# LPC812_breakout_v0_8_no_lr.net
KiCad netlist of a schematic drawn in EAGLE
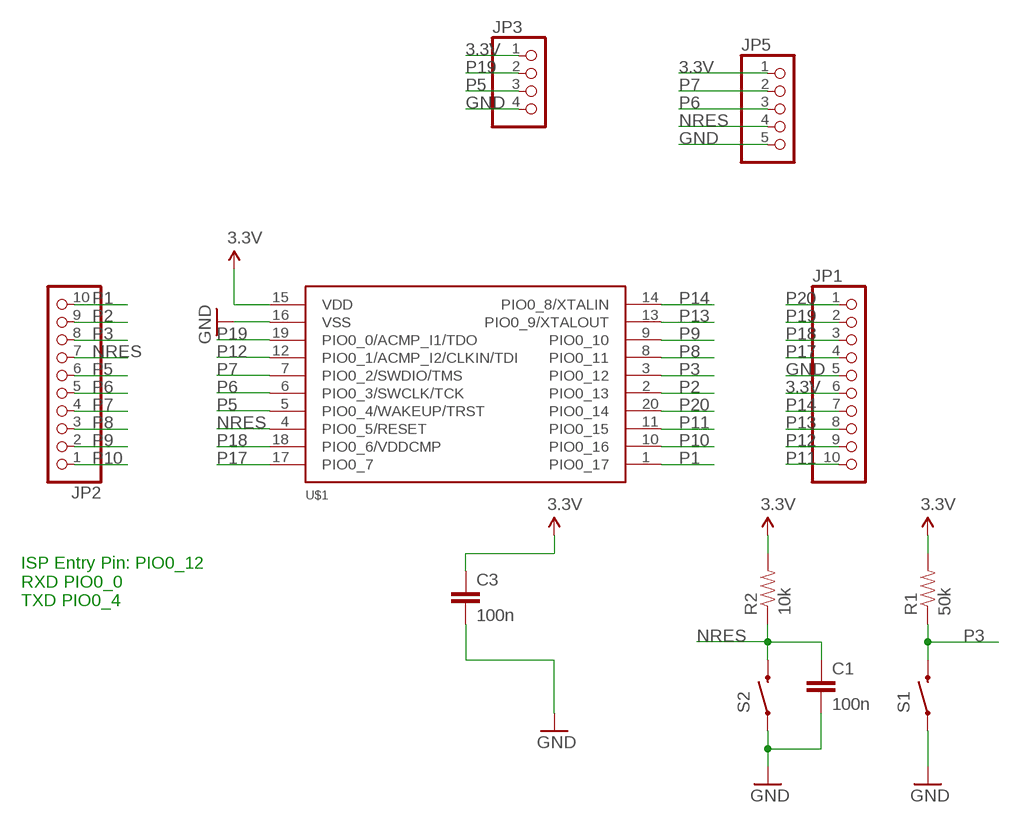
[diagram p0: schematic, sheet 1]

(export (version "E")
  (design (tool "Eeschema 10.0.6"))
  (components
    (comp (ref "C1")
      (value "100n")
      (footprint "eagle-import:0805")
      (libsource (lib "eagle-import") (part "CAP0805"))
    )
    (comp (ref "C3")
      (value "100n")
      (footprint "eagle-import:0805")
      (libsource (lib "eagle-import") (part "CAP0805"))
    )
    (comp (ref "JP1")
      (value "HEADER-1X10ROUND")
      (footprint "eagle-import:1X10_ROUND")
      (libsource (lib "eagle-import") (part "HEADER-1X10ROUND"))
    )
    (comp (ref "JP2")
      (value "HEADER-1X10ROUND")
      (footprint "eagle-import:1X10_ROUND")
      (libsource (lib "eagle-import") (part "HEADER-1X10ROUND"))
    )
    (comp (ref "JP3")
      (value "HEADER-1X4ROUND")
      (footprint "eagle-import:1X04_ROUND")
      (libsource (lib "eagle-import") (part "HEADER-1X4ROUND"))
    )
    (comp (ref "JP5")
      (value "HEADER-1X5ROUND")
      (footprint "eagle-import:1X05_ROUND")
      (libsource (lib "eagle-import") (part "HEADER-1X5ROUND"))
    )
    (comp (ref "R1")
      (value "50k")
      (footprint "eagle-import:0805")
      (libsource (lib "eagle-import") (part "RESISTOR0805-RES"))
    )
    (comp (ref "R2")
      (value "10k")
      (footprint "eagle-import:0805")
      (libsource (lib "eagle-import") (part "RESISTOR0805-RES"))
    )
    (comp (ref "S1")
      (value "SWITCH-MOMENTARY-2-SMD-1101NE")
      (footprint "eagle-import:TACTILE-SWITCH-1101NE")
      (libsource (lib "eagle-import") (part "SWITCH-MOMENTARY-2-SMD-1101NE"))
    )
    (comp (ref "S2")
      (value "SWITCH-MOMENTARY-2-SMD-1101NE")
      (footprint "eagle-import:TACTILE-SWITCH-1101NE")
      (libsource (lib "eagle-import") (part "SWITCH-MOMENTARY-2-SMD-1101NE"))
    )
    (comp (ref "U$1")
      (value "LPC812M101JDH20")
      (footprint "eagle-import:TSSOP20")
      (libsource (lib "eagle-import") (part "LPC812M101JDH20"))
    )
  )
  (nets
    (net (code "1") (name "/NRES") (class "Default")
      (node (ref "C1") (pin "1") (pinfunction "1_1") (pintype "passive"))
      (node (ref "JP2") (pin "7") (pinfunction "7_7") (pintype "passive"))
      (node (ref "JP5") (pin "4") (pinfunction "4_4") (pintype "passive"))
      (node (ref "R2") (pin "1") (pinfunction "1_1") (pintype "passive"))
      (node (ref "S2") (pin "P$2") (pinfunction "2_P$2") (pintype "passive"))
      (node (ref "U$1") (pin "4") (pinfunction "PIO0_5/RESET_4") (pintype "bidirectional"))
    )
    (net (code "2") (name "/P1") (class "Default")
      (node (ref "JP2") (pin "10") (pinfunction "10_10") (pintype "passive"))
      (node (ref "U$1") (pin "1") (pinfunction "PIO0_17_1") (pintype "bidirectional"))
    )
    (net (code "3") (name "/P2") (class "Default")
      (node (ref "JP2") (pin "9") (pinfunction "9_9") (pintype "passive"))
      (node (ref "U$1") (pin "2") (pinfunction "PIO0_13_2") (pintype "bidirectional"))
    )
    (net (code "4") (name "/P3") (class "Default")
      (node (ref "JP2") (pin "8") (pinfunction "8_8") (pintype "passive"))
      (node (ref "R1") (pin "1") (pinfunction "1_1") (pintype "passive"))
      (node (ref "S1") (pin "P$2") (pinfunction "2_P$2") (pintype "passive"))
      (node (ref "U$1") (pin "3") (pinfunction "PIO0_12_3") (pintype "bidirectional"))
    )
    (net (code "5") (name "/P5") (class "Default")
      (node (ref "JP2") (pin "6") (pinfunction "6_6") (pintype "passive"))
      (node (ref "JP3") (pin "3") (pinfunction "3_3") (pintype "passive"))
      (node (ref "U$1") (pin "5") (pinfunction "PIO0_4/WAKEUP/TRST_5") (pintype "bidirectional"))
    )
    (net (code "6") (name "/P6") (class "Default")
      (node (ref "JP2") (pin "5") (pinfunction "5_5") (pintype "passive"))
      (node (ref "JP5") (pin "3") (pinfunction "3_3") (pintype "passive"))
      (node (ref "U$1") (pin "6") (pinfunction "PIO0_3/SWCLK/TCK_6") (pintype "bidirectional"))
    )
    (net (code "7") (name "/P7") (class "Default")
      (node (ref "JP2") (pin "4") (pinfunction "4_4") (pintype "passive"))
      (node (ref "JP5") (pin "2") (pinfunction "2_2") (pintype "passive"))
      (node (ref "U$1") (pin "7") (pinfunction "PIO0_2/SWDIO/TMS_7") (pintype "bidirectional"))
    )
    (net (code "8") (name "/P8") (class "Default")
      (node (ref "JP2") (pin "3") (pinfunction "3_3") (pintype "passive"))
      (node (ref "U$1") (pin "8") (pinfunction "PIO0_11_8") (pintype "bidirectional"))
    )
    (net (code "9") (name "/P9") (class "Default")
      (node (ref "JP2") (pin "2") (pinfunction "2_2") (pintype "passive"))
      (node (ref "U$1") (pin "9") (pinfunction "PIO0_10_9") (pintype "bidirectional"))
    )
    (net (code "10") (name "/P10") (class "Default")
      (node (ref "JP2") (pin "1") (pinfunction "1_1") (pintype "passive"))
      (node (ref "U$1") (pin "10") (pinfunction "PIO0_16_10") (pintype "bidirectional"))
    )
    (net (code "11") (name "/P11") (class "Default")
      (node (ref "JP1") (pin "10") (pinfunction "10_10") (pintype "passive"))
      (node (ref "U$1") (pin "11") (pinfunction "PIO0_15_11") (pintype "bidirectional"))
    )
    (net (code "12") (name "/P12") (class "Default")
      (node (ref "JP1") (pin "9") (pinfunction "9_9") (pintype "passive"))
      (node (ref "U$1") (pin "12") (pinfunction "PIO0_1/ACMP_I2/CLKIN/TDI_12") (pintype "bidirectional"))
    )
    (net (code "13") (name "/P13") (class "Default")
      (node (ref "JP1") (pin "8") (pinfunction "8_8") (pintype "passive"))
      (node (ref "U$1") (pin "13") (pinfunction "PIO0_9/XTALOUT_13") (pintype "bidirectional"))
    )
    (net (code "14") (name "/P14") (class "Default")
      (node (ref "JP1") (pin "7") (pinfunction "7_7") (pintype "passive"))
      (node (ref "U$1") (pin "14") (pinfunction "PIO0_8/XTALIN_14") (pintype "bidirectional"))
    )
    (net (code "15") (name "/P17") (class "Default")
      (node (ref "JP1") (pin "4") (pinfunction "4_4") (pintype "passive"))
      (node (ref "U$1") (pin "17") (pinfunction "PIO0_7_17") (pintype "bidirectional"))
    )
    (net (code "16") (name "/P18") (class "Default")
      (node (ref "JP1") (pin "3") (pinfunction "3_3") (pintype "passive"))
      (node (ref "U$1") (pin "18") (pinfunction "PIO0_6/VDDCMP_18") (pintype "bidirectional"))
    )
    (net (code "17") (name "/P19") (class "Default")
      (node (ref "JP1") (pin "2") (pinfunction "2_2") (pintype "passive"))
      (node (ref "JP3") (pin "2") (pinfunction "2_2") (pintype "passive"))
      (node (ref "U$1") (pin "19") (pinfunction "PIO0_0/ACMP_I1/TDO_19") (pintype "bidirectional"))
    )
    (net (code "18") (name "/P20") (class "Default")
      (node (ref "JP1") (pin "1") (pinfunction "1_1") (pintype "passive"))
      (node (ref "U$1") (pin "20") (pinfunction "PIO0_14_20") (pintype "bidirectional"))
    )
    (net (code "19") (name "3.3V") (class "Default")
      (node (ref "C3") (pin "1") (pinfunction "1_1") (pintype "passive"))
      (node (ref "JP1") (pin "6") (pinfunction "6_6") (pintype "passive"))
      (node (ref "JP3") (pin "1") (pinfunction "1_1") (pintype "passive"))
      (node (ref "JP5") (pin "1") (pinfunction "1_1") (pintype "passive"))
      (node (ref "R1") (pin "2") (pinfunction "2_2") (pintype "passive"))
      (node (ref "R2") (pin "2") (pinfunction "2_2") (pintype "passive"))
      (node (ref "U$1") (pin "15") (pinfunction "VDD_15") (pintype "bidirectional"))
    )
    (net (code "20") (name "GND") (class "Default")
      (node (ref "C1") (pin "2") (pinfunction "2_2") (pintype "passive"))
      (node (ref "C3") (pin "2") (pinfunction "2_2") (pintype "passive"))
      (node (ref "JP1") (pin "5") (pinfunction "5_5") (pintype "passive"))
      (node (ref "JP3") (pin "4") (pinfunction "4_4") (pintype "passive"))
      (node (ref "JP5") (pin "5") (pinfunction "5_5") (pintype "passive"))
      (node (ref "S1") (pin "P$1") (pinfunction "1_P$1") (pintype "passive"))
      (node (ref "S2") (pin "P$1") (pinfunction "1_P$1") (pintype "passive"))
      (node (ref "U$1") (pin "16") (pinfunction "VSS_16") (pintype "bidirectional"))
    )
  )
)
